# DC-DC_Converter.net
KiCad netlist of a schematic drawn in Altium Designer
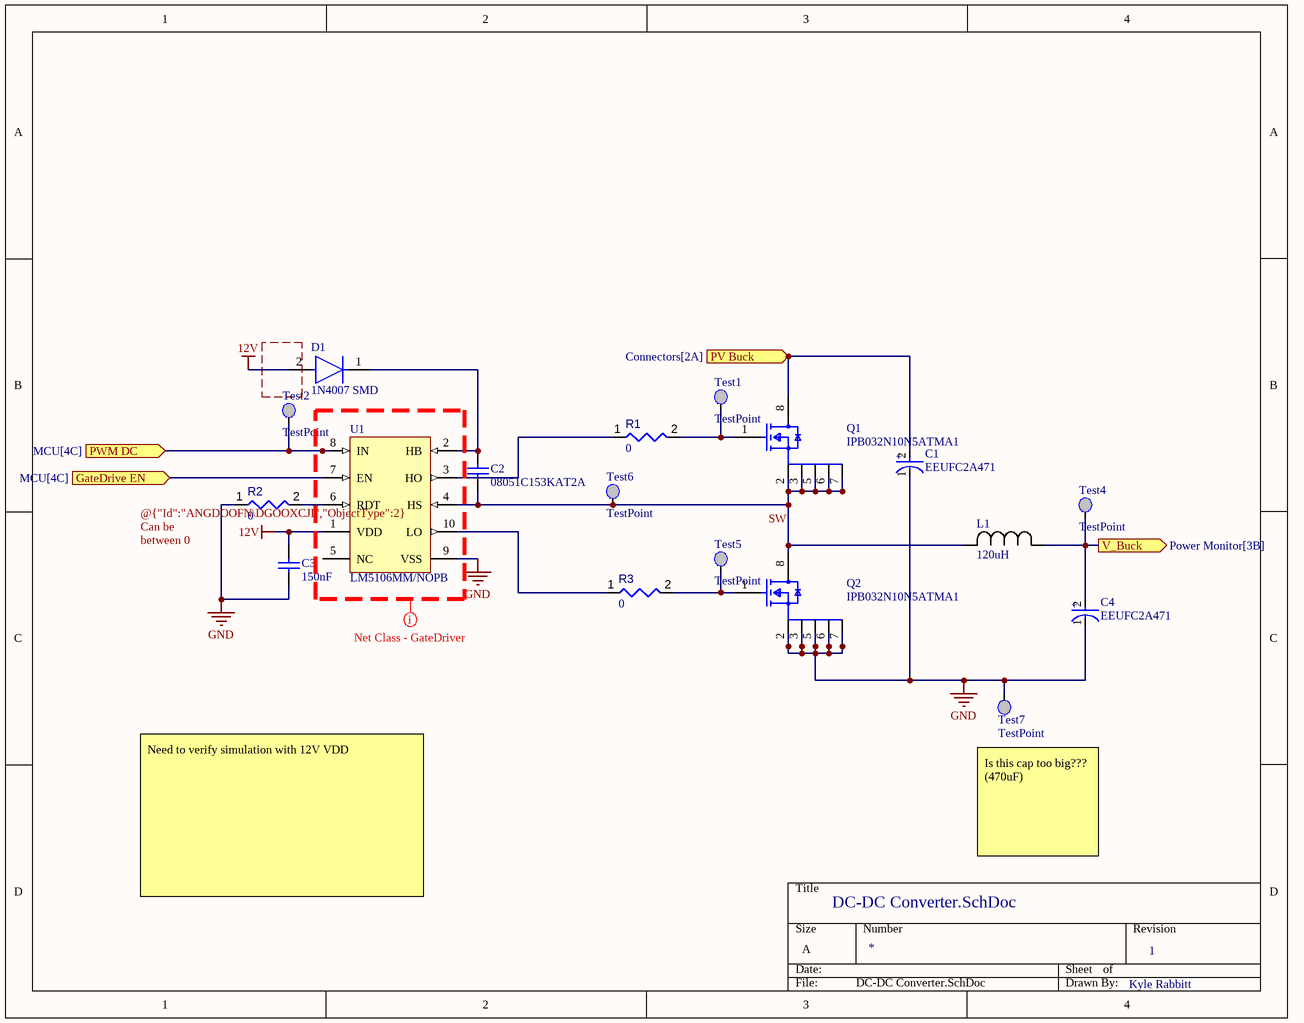
[diagram p0: DC-DC Converter.SchDoc]

(export (version "E")
  (design (tool "Eeschema 10.0.6"))
  (components
    (comp (ref "C1")
      (value "EEUFC2A471")
      (footprint "FP-RAD-TH-D_16_0_5-L_40_2-MFG")
      (description "Aluminum Electrolytic Capacitors (Radial Lead Type) AEC-Q200 Qualified 470uF ±20% 100V")
      (fields (field (name "VOLTAGE") "100V") (field (name "TOLERANCE") "20%"))
      (libsource (lib "Altium Content Vault") (part "203bc49f2ac43e59fd269a8c329ed05"))
    )
    (comp (ref "C2")
      (value "08051C153KAT2A")
      (footprint "CAPC2013X94X50NL20T25")
      (description "15nF / 0.01uF")
      (fields (field (name "MANUFACTURER") "AVX Interconnect / Elco"))
      (libsource (lib "Altium Content Vault") (part "CAP"))
    )
    (comp (ref "C3")
      (value "150nF")
      (footprint "CAPC2013X140X50LL20T25")
      (description "08053C154KAT2A")
      (fields (field (name "MANUFACTURER") "AVX Interconnect / Elco"))
      (libsource (lib "Altium Content Vault") (part "CAP"))
    )
    (comp (ref "C4")
      (value "EEUFC2A471")
      (footprint "FP-RAD-TH-D_16_0_5-L_40_2-MFG")
      (description "Aluminum Electrolytic Capacitors (Radial Lead Type) AEC-Q200 Qualified 470uF ±20% 100V")
      (fields (field (name "VOLTAGE") "100V") (field (name "TOLERANCE") "20%"))
      (libsource (lib "Altium Content Vault") (part "203bc49f2ac43e59fd269a8c329ed05"))
    )
    (comp (ref "D1")
      (value "1N4007 SMD")
      (footprint "FP-1N4007_SMD-IPC_C")
      (description "Rectifier, 1Kv, 1A, Do-214Ac Rohs Compliant: Yes")
      (libsource (lib "Altium Content Vault") (part "d7152d700b627762746794eb795d46e"))
    )
    (comp (ref "L1")
      (value "120uH")
      (footprint "IND_2300HT-V_56_42")
      (description "120uH\r\n2300HT-121-V-RC")
      (libsource (lib "2300HT-121-V-RC") (part "2300HT-121-V-RC"))
    )
    (comp (ref "Q1")
      (value "IPB032N10N5ATMA1")
      (footprint "FP-PG-TO263-7-MFG")
      (description "MOSFET N-CH 100V 166A TO263-7")
      (libsource (lib "Altium Content Vault") (part "903eed33892df4550160e7e4e4a3e2a"))
    )
    (comp (ref "Q2")
      (value "IPB032N10N5ATMA1")
      (footprint "FP-PG-TO263-7-MFG")
      (description "MOSFET N-CH 100V 166A TO263-7")
      (libsource (lib "Altium Content Vault") (part "903eed33892df4550160e7e4e4a3e2a"))
    )
    (comp (ref "R1")
      (value "0")
      (footprint "RESC0603(1608)_L")
      (description "Jumper 0603 (1608 Metric)")
      (fields (field (name "Comment") "0R3J"))
      (libsource (lib "WPI High Power Rocketry Club") (part "0R3J"))
    )
    (comp (ref "R2")
      (value "0")
      (footprint "RESC0603(1608)_L")
      (description "Jumper 0603 (1608 Metric)")
      (fields (field (name "Comment") "0R3J"))
      (libsource (lib "WPI High Power Rocketry Club") (part "0R3J"))
    )
    (comp (ref "R3")
      (value "0")
      (footprint "RESC0603(1608)_L")
      (description "Jumper 0603 (1608 Metric)")
      (fields (field (name "Comment") "0R3J"))
      (libsource (lib "WPI High Power Rocketry Club") (part "0R3J"))
    )
    (comp (ref "Test1")
      (value "TestPoint")
      (footprint "Test_IN")
      (libsource (lib "Test_POINTS") (part "TestPoint"))
    )
    (comp (ref "Test2")
      (value "TestPoint")
      (footprint "Test_IN")
      (libsource (lib "Test_POINTS") (part "TestPoint"))
    )
    (comp (ref "Test4")
      (value "TestPoint")
      (footprint "Test_IN")
      (libsource (lib "Test_POINTS") (part "TestPoint"))
    )
    (comp (ref "Test5")
      (value "TestPoint")
      (footprint "Test_IN")
      (libsource (lib "Test_POINTS") (part "TestPoint"))
    )
    (comp (ref "Test6")
      (value "TestPoint")
      (footprint "Test_IN")
      (libsource (lib "Test_POINTS") (part "TestPoint"))
    )
    (comp (ref "Test7")
      (value "TestPoint")
      (footprint "Test_IN")
      (libsource (lib "Test_POINTS") (part "TestPoint"))
    )
    (comp (ref "U1")
      (value "LM5106MM/NOPB")
      (footprint "DGS0010A_N")
      (description "100V Half-Bridge Gate Driver with Programmable Dead-Time, 10-pin MSOP, Pb-Free")
      (fields (field (name "MANUFACTURER") "Texas Instruments"))
      (libsource (lib "Altium Content Vault") (part "IN-MOSDRV-LM5106-10"))
    )
  )
  (nets
    (net (code "1") (name "/GateDrive EN") (class "Default")
      (node (ref "U1") (pin "7") (pinfunction "EN_7") (pintype "input"))
    )
    (net (code "2") (name "/PV Buck") (class "Default")
      (node (ref "C1") (pin "2") (pinfunction "A_2") (pintype "passive"))
      (node (ref "Q1") (pin "8") (pinfunction "DRAIN_8") (pintype "passive"))
    )
    (net (code "3") (name "/PWM DC") (class "Default")
      (node (ref "Test2") (pin "IN") (pinfunction "IN_IN") (pintype "input"))
      (node (ref "U1") (pin "8") (pinfunction "IN_8") (pintype "input"))
    )
    (net (code "4") (name "/SW") (class "Default")
      (node (ref "C2") (pin "1") (pinfunction "1_1") (pintype "passive"))
      (node (ref "L1") (pin "2") (pinfunction "2_2") (pintype "passive"))
      (node (ref "Q1") (pin "2") (pinfunction "SOURCE_2") (pintype "passive"))
      (node (ref "Q1") (pin "3") (pinfunction "SOURCE_3") (pintype "passive"))
      (node (ref "Q1") (pin "5") (pinfunction "SOURCE_5") (pintype "passive"))
      (node (ref "Q1") (pin "6") (pinfunction "SOURCE_6") (pintype "passive"))
      (node (ref "Q1") (pin "7") (pinfunction "SOURCE_7") (pintype "passive"))
      (node (ref "Q2") (pin "8") (pinfunction "DRAIN_8") (pintype "passive"))
      (node (ref "Test6") (pin "IN") (pinfunction "IN_IN") (pintype "input"))
      (node (ref "U1") (pin "4") (pinfunction "HS_4") (pintype "input"))
    )
    (net (code "5") (name "/V_Buck") (class "Default")
      (node (ref "C4") (pin "2") (pinfunction "A_2") (pintype "passive"))
      (node (ref "L1") (pin "1") (pinfunction "1_1") (pintype "passive"))
      (node (ref "Test4") (pin "IN") (pinfunction "IN_IN") (pintype "input"))
    )
    (net (code "6") (name "12V") (class "Default")
      (node (ref "C3") (pin "2") (pinfunction "2_2") (pintype "passive"))
      (node (ref "D1") (pin "2") (pinfunction "A_2") (pintype "passive"))
      (node (ref "U1") (pin "1") (pinfunction "VDD_1") (pintype "power_in"))
    )
    (net (code "7") (name "GND") (class "Default")
      (node (ref "C1") (pin "1") (pinfunction "C_1") (pintype "passive"))
      (node (ref "C3") (pin "1") (pinfunction "1_1") (pintype "passive"))
      (node (ref "C4") (pin "1") (pinfunction "C_1") (pintype "passive"))
      (node (ref "Q2") (pin "2") (pinfunction "SOURCE_2") (pintype "passive"))
      (node (ref "Q2") (pin "3") (pinfunction "SOURCE_3") (pintype "passive"))
      (node (ref "Q2") (pin "5") (pinfunction "SOURCE_5") (pintype "passive"))
      (node (ref "Q2") (pin "6") (pinfunction "SOURCE_6") (pintype "passive"))
      (node (ref "Q2") (pin "7") (pinfunction "SOURCE_7") (pintype "passive"))
      (node (ref "R2") (pin "1") (pinfunction "1_1") (pintype "passive"))
      (node (ref "Test7") (pin "IN") (pinfunction "IN_IN") (pintype "input"))
      (node (ref "U1") (pin "9") (pinfunction "VSS_9") (pintype "power_in"))
    )
    (net (code "8") (name "Net-(D1-C)") (class "Default")
      (node (ref "C2") (pin "2") (pinfunction "2_2") (pintype "passive"))
      (node (ref "D1") (pin "1") (pinfunction "C_1") (pintype "passive"))
      (node (ref "U1") (pin "2") (pinfunction "HB_2") (pintype "input"))
    )
    (net (code "9") (name "Net-(Q1-GATE)") (class "Default")
      (node (ref "Q1") (pin "1") (pinfunction "GATE_1") (pintype "passive"))
      (node (ref "R1") (pin "2") (pinfunction "2_2") (pintype "passive"))
      (node (ref "Test1") (pin "IN") (pinfunction "IN_IN") (pintype "input"))
    )
    (net (code "10") (name "Net-(Q2-GATE)") (class "Default")
      (node (ref "Q2") (pin "1") (pinfunction "GATE_1") (pintype "passive"))
      (node (ref "R3") (pin "2") (pinfunction "2_2") (pintype "passive"))
      (node (ref "Test5") (pin "IN") (pinfunction "IN_IN") (pintype "input"))
    )
    (net (code "11") (name "Net-(U1-HO)") (class "Default")
      (node (ref "R1") (pin "1") (pinfunction "1_1") (pintype "passive"))
      (node (ref "U1") (pin "3") (pinfunction "HO_3") (pintype "output"))
    )
    (net (code "12") (name "Net-(U1-LO)") (class "Default")
      (node (ref "R3") (pin "1") (pinfunction "1_1") (pintype "passive"))
      (node (ref "U1") (pin "10") (pinfunction "LO_10") (pintype "output"))
    )
    (net (code "13") (name "Net-(U1-RDT)") (class "Default")
      (node (ref "R2") (pin "2") (pinfunction "2_2") (pintype "passive"))
      (node (ref "U1") (pin "6") (pinfunction "RDT_6") (pintype "input"))
    )
    (net (code "14") (name "unconnected-(U1-NC-Pad5)") (class "Default")
      (node (ref "U1") (pin "5") (pinfunction "NC_5") (pintype "passive"))
    )
  )
)
